# Blow_out_LED_tree_-_test_circuit_v1.net
KiCad netlist of a schematic drawn in EAGLE
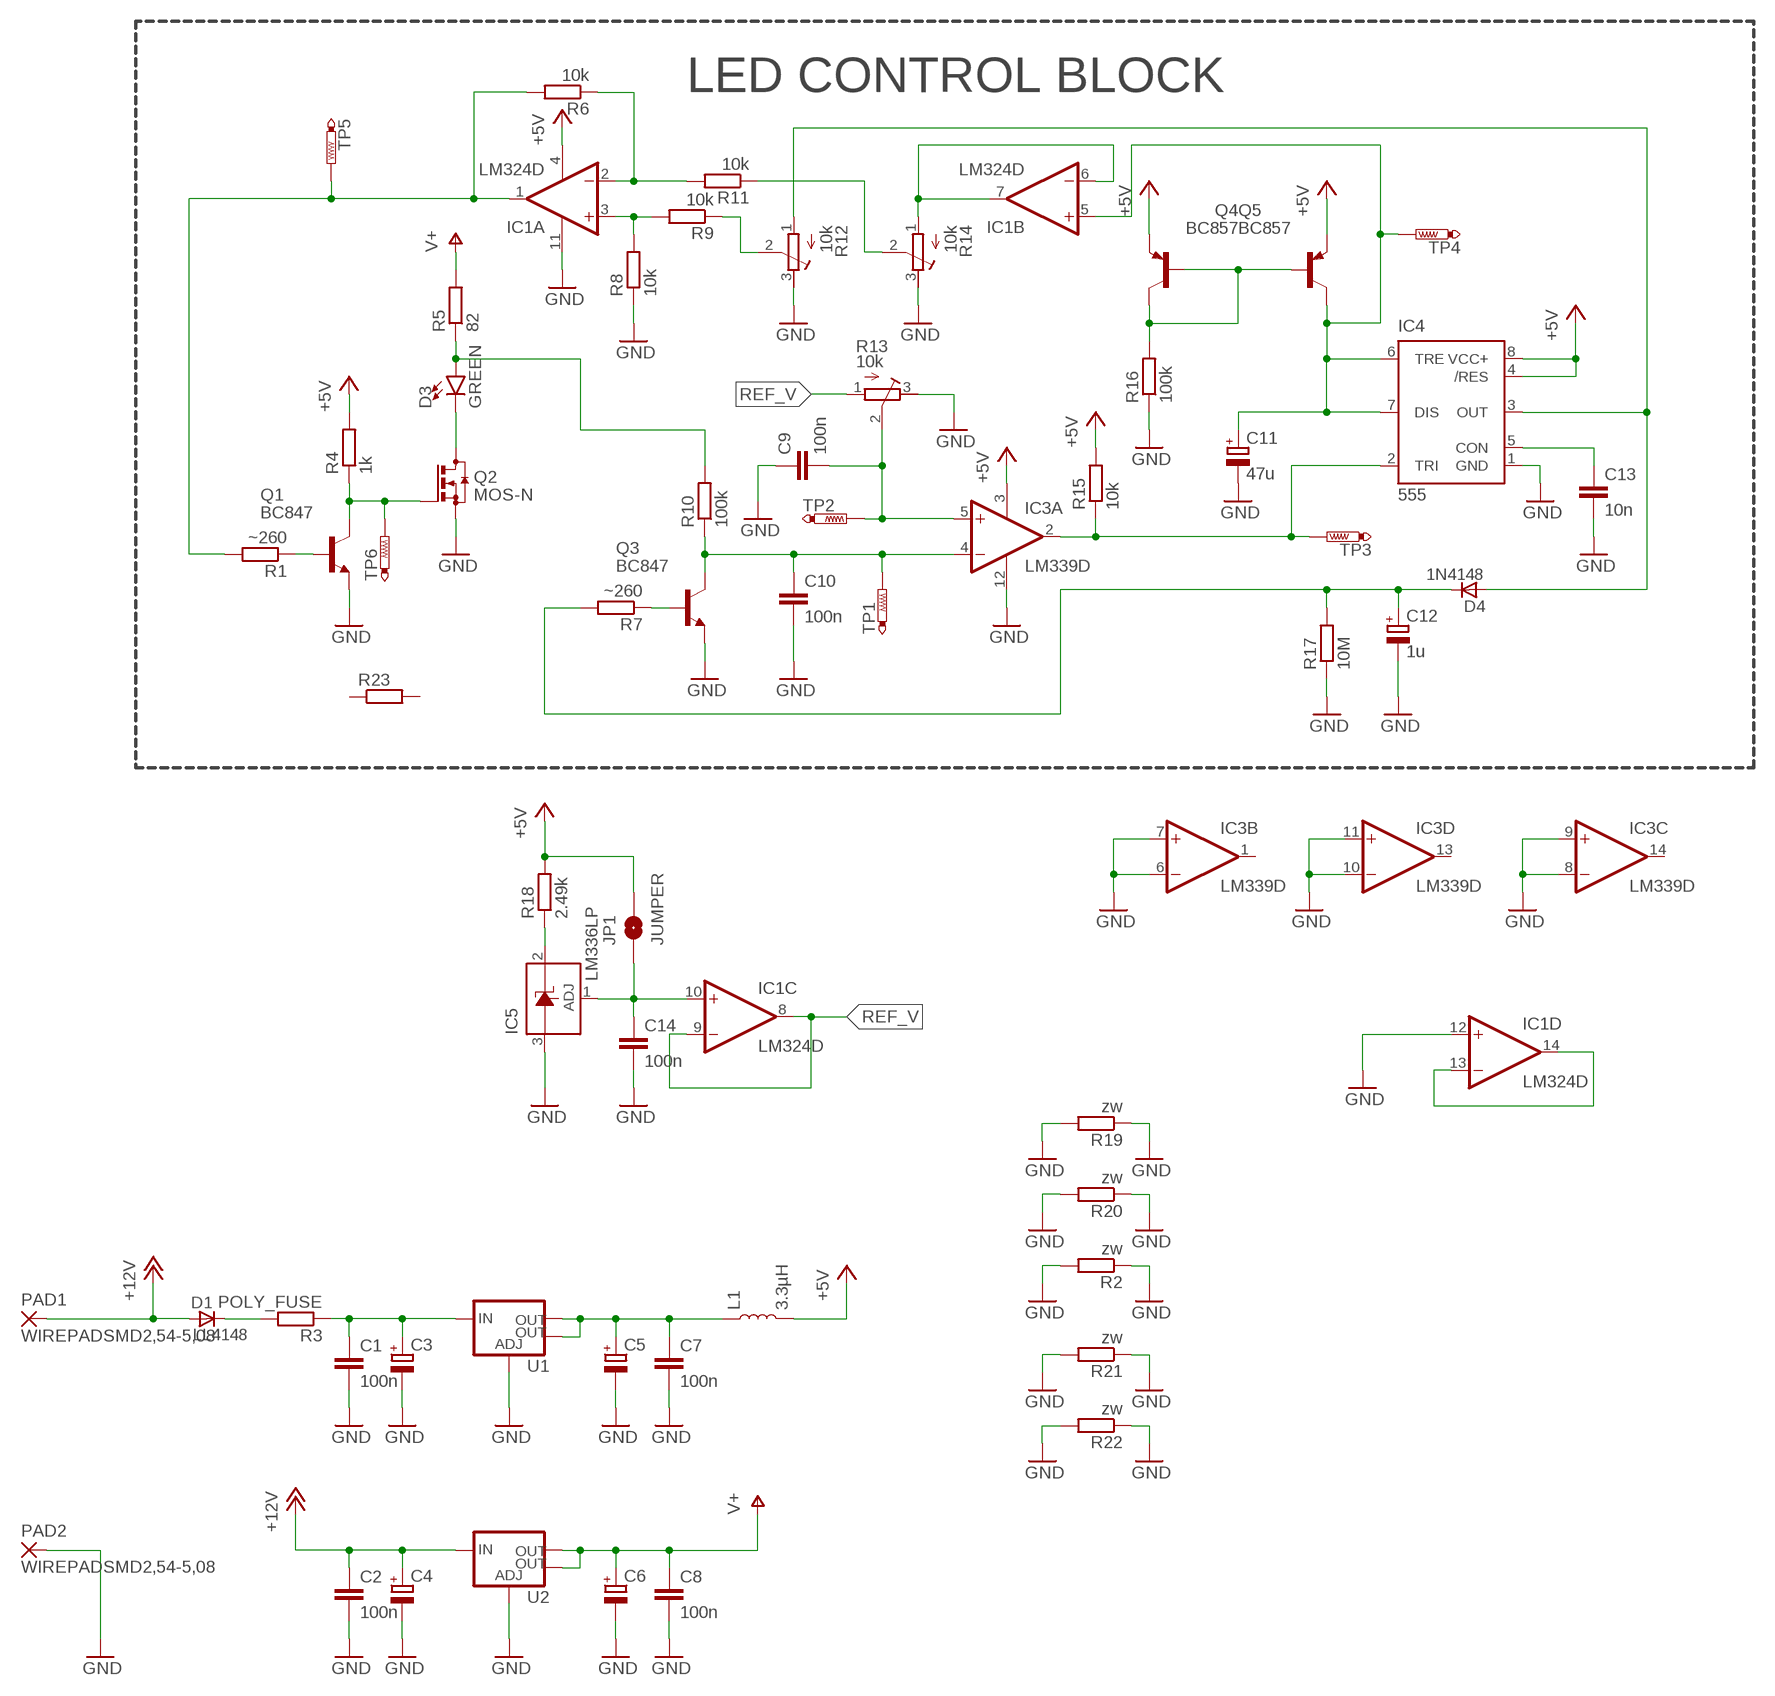
[diagram p0: schematic, sheet 1]

(export (version "E")
  (design (tool "Eeschema 10.0.6"))
  (components
    (comp (ref "C1")
      (value "100n")
      (footprint "eagle-import:C1206")
      (libsource (lib "eagle-import") (part "C-EUC1206"))
    )
    (comp (ref "C2")
      (value "100n")
      (footprint "eagle-import:C1206")
      (libsource (lib "eagle-import") (part "C-EUC1206"))
    )
    (comp (ref "C3")
      (value "CPOL-EU153CLV-0810")
      (footprint "eagle-import:153CLV-0810")
      (libsource (lib "eagle-import") (part "CPOL-EU153CLV-0810"))
    )
    (comp (ref "C4")
      (value "CPOL-EU153CLV-0810")
      (footprint "eagle-import:153CLV-0810")
      (libsource (lib "eagle-import") (part "CPOL-EU153CLV-0810"))
    )
    (comp (ref "C5")
      (value "CPOL-EU153CLV-0810")
      (footprint "eagle-import:153CLV-0810")
      (libsource (lib "eagle-import") (part "CPOL-EU153CLV-0810"))
    )
    (comp (ref "C6")
      (value "CPOL-EU153CLV-0810")
      (footprint "eagle-import:153CLV-0810")
      (libsource (lib "eagle-import") (part "CPOL-EU153CLV-0810"))
    )
    (comp (ref "C7")
      (value "100n")
      (footprint "eagle-import:C1206")
      (libsource (lib "eagle-import") (part "C-EUC1206"))
    )
    (comp (ref "C8")
      (value "100n")
      (footprint "eagle-import:C1206")
      (libsource (lib "eagle-import") (part "C-EUC1206"))
    )
    (comp (ref "C9")
      (value "100n")
      (footprint "eagle-import:C1206")
      (libsource (lib "eagle-import") (part "C-EUC1206"))
    )
    (comp (ref "C10")
      (value "100n")
      (footprint "eagle-import:C1206")
      (libsource (lib "eagle-import") (part "C-EUC1206"))
    )
    (comp (ref "C11")
      (value "47u")
      (footprint "eagle-import:153CLV-0605")
      (libsource (lib "eagle-import") (part "CPOL-EU153CLV-0605"))
    )
    (comp (ref "C12")
      (value "1u")
      (footprint "eagle-import:153CLV-0605")
      (libsource (lib "eagle-import") (part "CPOL-EU153CLV-0605"))
    )
    (comp (ref "C13")
      (value "10n")
      (footprint "eagle-import:C1206")
      (libsource (lib "eagle-import") (part "C-EUC1206"))
    )
    (comp (ref "C14")
      (value "100n")
      (footprint "eagle-import:C1206")
      (libsource (lib "eagle-import") (part "C-EUC1206"))
    )
    (comp (ref "D1")
      (value "LL4148")
      (footprint "eagle-import:SOD80_DO213AA_MINIMELF")
      (libsource (lib "eagle-import") (part "LL4148"))
    )
    (comp (ref "D3")
      (value "GREEN")
      (footprint "eagle-import:FKIT-LED-1206")
      (libsource (lib "eagle-import") (part "LED-FKIT-1206"))
    )
    (comp (ref "D4")
      (value "1N4148")
      (footprint "eagle-import:SOD80_DO213AA_MINIMELF")
      (libsource (lib "eagle-import") (part "LL4148"))
    )
    (comp (ref "IC1")
      (value "LM324D")
      (footprint "eagle-import:SO14")
      (libsource (lib "eagle-import") (part "LM324D"))
    )
    (comp (ref "IC3")
      (value "LM339D")
      (footprint "eagle-import:SO14")
      (libsource (lib "eagle-import") (part "LM339D"))
    )
    (comp (ref "IC4")
      (value "555")
      (footprint "eagle-import:SO08")
      (libsource (lib "eagle-import") (part "555D"))
    )
    (comp (ref "IC5")
      (value "LM336LP")
      (footprint "eagle-import:TO92")
      (libsource (lib "eagle-import") (part "LM336LP"))
    )
    (comp (ref "JP1")
      (value "JUMPER")
      (footprint "eagle-import:SMT-JUMPER_2_NO_NO-SILK_ROUND")
      (libsource (lib "eagle-import") (part "JUMPER-SMT_2_NO_NO-SILK_ROUND"))
    )
    (comp (ref "L1")
      (value "3.3µH")
      (footprint "eagle-import:0805")
      (libsource (lib "eagle-import") (part "INDUCTOR-0805-3.3UH"))
    )
    (comp (ref "PAD1")
      (value "WIREPADSMD2,54-5,08")
      (footprint "eagle-import:SMD2,54-5,08")
      (libsource (lib "eagle-import") (part "WIREPADSMD2,54-5,08"))
    )
    (comp (ref "PAD2")
      (value "WIREPADSMD2,54-5,08")
      (footprint "eagle-import:SMD2,54-5,08")
      (libsource (lib "eagle-import") (part "WIREPADSMD2,54-5,08"))
    )
    (comp (ref "Q1")
      (value "BC847")
      (footprint "eagle-import:SOT23")
      (libsource (lib "eagle-import") (part "BC847SMDA"))
    )
    (comp (ref "Q2")
      (value "MOS-N")
      (footprint "eagle-import:SOT23")
      (libsource (lib "eagle-import") (part "BSS123"))
    )
    (comp (ref "Q3")
      (value "BC847")
      (footprint "eagle-import:SOT23")
      (libsource (lib "eagle-import") (part "BC847SMDA"))
    )
    (comp (ref "Q4")
      (value "BC857")
      (footprint "eagle-import:SOT23-BEC")
      (libsource (lib "eagle-import") (part "BC857SMDALT1"))
    )
    (comp (ref "Q5")
      (value "BC857")
      (footprint "eagle-import:SOT23-BEC")
      (libsource (lib "eagle-import") (part "BC857SMDALT1"))
    )
    (comp (ref "R1")
      (value "~260")
      (footprint "eagle-import:R1206")
      (libsource (lib "eagle-import") (part "R-EU_R1206"))
    )
    (comp (ref "R2")
      (value "zw")
      (footprint "eagle-import:R1206")
      (libsource (lib "eagle-import") (part "R-EU_R1206"))
    )
    (comp (ref "R3")
      (value "POLY_FUSE")
      (footprint "eagle-import:R1206")
      (libsource (lib "eagle-import") (part "R-EU_R1206"))
    )
    (comp (ref "R4")
      (value "1k")
      (footprint "eagle-import:R1206")
      (libsource (lib "eagle-import") (part "R-EU_R1206"))
    )
    (comp (ref "R5")
      (value "82")
      (footprint "eagle-import:R1206")
      (libsource (lib "eagle-import") (part "R-EU_R1206"))
    )
    (comp (ref "R6")
      (value "10k")
      (footprint "eagle-import:R1206")
      (libsource (lib "eagle-import") (part "R-EU_R1206"))
    )
    (comp (ref "R7")
      (value "~260")
      (footprint "eagle-import:R1206")
      (libsource (lib "eagle-import") (part "R-EU_R1206"))
    )
    (comp (ref "R8")
      (value "10k")
      (footprint "eagle-import:R1206")
      (libsource (lib "eagle-import") (part "R-EU_R1206"))
    )
    (comp (ref "R9")
      (value "10k")
      (footprint "eagle-import:R1206")
      (libsource (lib "eagle-import") (part "R-EU_R1206"))
    )
    (comp (ref "R10")
      (value "100k")
      (footprint "eagle-import:R1206")
      (libsource (lib "eagle-import") (part "R-EU_R1206"))
    )
    (comp (ref "R11")
      (value "10k")
      (footprint "eagle-import:R1206")
      (libsource (lib "eagle-import") (part "R-EU_R1206"))
    )
    (comp (ref "R12")
      (value "10k")
      (footprint "eagle-import:RTRIM3374")
      (libsource (lib "eagle-import") (part "R-TRIMM3374"))
    )
    (comp (ref "R13")
      (value "10k")
      (footprint "eagle-import:RTRIM3374")
      (libsource (lib "eagle-import") (part "R-TRIMM3374"))
    )
    (comp (ref "R14")
      (value "10k")
      (footprint "eagle-import:RTRIM3374")
      (libsource (lib "eagle-import") (part "R-TRIMM3374"))
    )
    (comp (ref "R15")
      (value "10k")
      (footprint "eagle-import:R1206")
      (libsource (lib "eagle-import") (part "R-EU_R1206"))
    )
    (comp (ref "R16")
      (value "100k")
      (footprint "eagle-import:R1206")
      (libsource (lib "eagle-import") (part "R-EU_R1206"))
    )
    (comp (ref "R17")
      (value "10M")
      (footprint "eagle-import:R1206")
      (libsource (lib "eagle-import") (part "R-EU_R1206"))
    )
    (comp (ref "R18")
      (value "2.49k")
      (footprint "eagle-import:R1206")
      (libsource (lib "eagle-import") (part "R-EU_R1206"))
    )
    (comp (ref "R19")
      (value "zw")
      (footprint "eagle-import:R1206")
      (libsource (lib "eagle-import") (part "R-EU_R1206"))
    )
    (comp (ref "R20")
      (value "zw")
      (footprint "eagle-import:R1206")
      (libsource (lib "eagle-import") (part "R-EU_R1206"))
    )
    (comp (ref "R21")
      (value "zw")
      (footprint "eagle-import:R1206")
      (libsource (lib "eagle-import") (part "R-EU_R1206"))
    )
    (comp (ref "R22")
      (value "zw")
      (footprint "eagle-import:R1206")
      (libsource (lib "eagle-import") (part "R-EU_R1206"))
    )
    (comp (ref "R23")
      (value "R-EU_R0603")
      (footprint "eagle-import:R0603")
      (libsource (lib "eagle-import") (part "R-EU_R0603"))
    )
    (comp (ref "TP1")
      (value "PTR1B2,54")
      (footprint "eagle-import:B2,54")
      (libsource (lib "eagle-import") (part "PTR1B2,54"))
    )
    (comp (ref "TP2")
      (value "PTR1B2,54")
      (footprint "eagle-import:B2,54")
      (libsource (lib "eagle-import") (part "PTR1B2,54"))
    )
    (comp (ref "TP3")
      (value "PTR1B2,54")
      (footprint "eagle-import:B2,54")
      (libsource (lib "eagle-import") (part "PTR1B2,54"))
    )
    (comp (ref "TP4")
      (value "PTR1B2,54")
      (footprint "eagle-import:B2,54")
      (libsource (lib "eagle-import") (part "PTR1B2,54"))
    )
    (comp (ref "TP5")
      (value "PTR1B2,54")
      (footprint "eagle-import:B2,54")
      (libsource (lib "eagle-import") (part "PTR1B2,54"))
    )
    (comp (ref "TP6")
      (value "PTR1B2,54")
      (footprint "eagle-import:B2,54")
      (libsource (lib "eagle-import") (part "PTR1B2,54"))
    )
    (comp (ref "U1")
      (value "V_REG_LM1117SOT223")
      (footprint "eagle-import:SOT223")
      (libsource (lib "eagle-import") (part "V_REG_LM1117SOT223"))
    )
    (comp (ref "U2")
      (value "V_REG_LM1117SOT223")
      (footprint "eagle-import:SOT223")
      (libsource (lib "eagle-import") (part "V_REG_LM1117SOT223"))
    )
  )
  (nets
    (net (code "1") (name "+5V") (class "Default")
      (node (ref "IC1") (pin "4") (pinfunction "V+_4") (pintype "power_in"))
      (node (ref "IC3") (pin "3") (pinfunction "V+_3") (pintype "power_in"))
      (node (ref "IC4") (pin "4") (pinfunction "/RES_4") (pintype "input"))
      (node (ref "IC4") (pin "8") (pinfunction "VCC+_8") (pintype "power_in"))
      (node (ref "JP1") (pin "2") (pinfunction "2_2") (pintype "passive"))
      (node (ref "L1") (pin "2") (pinfunction "2_2") (pintype "passive"))
      (node (ref "Q4") (pin "E") (pinfunction "E_E") (pintype "passive"))
      (node (ref "Q5") (pin "E") (pinfunction "E_E") (pintype "passive"))
      (node (ref "R15") (pin "2") (pinfunction "2_2") (pintype "passive"))
      (node (ref "R18") (pin "2") (pinfunction "2_2") (pintype "passive"))
      (node (ref "R4") (pin "2") (pinfunction "2_2") (pintype "passive"))
    )
    (net (code "2") (name "+12V") (class "Default")
      (node (ref "C2") (pin "1") (pinfunction "1_1") (pintype "passive"))
      (node (ref "C4") (pin "+") (pinfunction "+_+") (pintype "passive"))
      (node (ref "D1") (pin "A") (pinfunction "A_A") (pintype "passive"))
      (node (ref "PAD1") (pin "1") (pinfunction "P_1") (pintype "passive"))
      (node (ref "U2") (pin "3") (pinfunction "IN_3") (pintype "input"))
    )
    (net (code "3") (name "GND") (class "Default")
      (node (ref "C1") (pin "2") (pinfunction "2_2") (pintype "passive"))
      (node (ref "C10") (pin "2") (pinfunction "2_2") (pintype "passive"))
      (node (ref "C11") (pin "-") (pinfunction "-_-") (pintype "passive"))
      (node (ref "C12") (pin "-") (pinfunction "-_-") (pintype "passive"))
      (node (ref "C13") (pin "2") (pinfunction "2_2") (pintype "passive"))
      (node (ref "C14") (pin "2") (pinfunction "2_2") (pintype "passive"))
      (node (ref "C2") (pin "2") (pinfunction "2_2") (pintype "passive"))
      (node (ref "C3") (pin "-") (pinfunction "-_-") (pintype "passive"))
      (node (ref "C4") (pin "-") (pinfunction "-_-") (pintype "passive"))
      (node (ref "C5") (pin "-") (pinfunction "-_-") (pintype "passive"))
      (node (ref "C6") (pin "-") (pinfunction "-_-") (pintype "passive"))
      (node (ref "C7") (pin "2") (pinfunction "2_2") (pintype "passive"))
      (node (ref "C8") (pin "2") (pinfunction "2_2") (pintype "passive"))
      (node (ref "C9") (pin "1") (pinfunction "1_1") (pintype "passive"))
      (node (ref "IC1") (pin "11") (pinfunction "V-_11") (pintype "power_in"))
      (node (ref "IC1") (pin "12") (pinfunction "+IN_12") (pintype "input"))
      (node (ref "IC3") (pin "10") (pinfunction "-IN_10") (pintype "input"))
      (node (ref "IC3") (pin "11") (pinfunction "+IN_11") (pintype "input"))
      (node (ref "IC3") (pin "12") (pinfunction "GND_12") (pintype "power_in"))
      (node (ref "IC3") (pin "6") (pinfunction "-IN_6") (pintype "input"))
      (node (ref "IC3") (pin "7") (pinfunction "+IN_7") (pintype "input"))
      (node (ref "IC3") (pin "8") (pinfunction "-IN_8") (pintype "input"))
      (node (ref "IC3") (pin "9") (pinfunction "+IN_9") (pintype "input"))
      (node (ref "IC4") (pin "1") (pinfunction "GND_1") (pintype "power_in"))
      (node (ref "IC5") (pin "3") (pinfunction "A_3") (pintype "input"))
      (node (ref "PAD2") (pin "1") (pinfunction "P_1") (pintype "passive"))
      (node (ref "Q1") (pin "2") (pinfunction "E_2") (pintype "passive"))
      (node (ref "Q2") (pin "2") (pinfunction "S_2") (pintype "passive"))
      (node (ref "Q3") (pin "2") (pinfunction "E_2") (pintype "passive"))
      (node (ref "R12") (pin "3") (pinfunction "E_3") (pintype "passive"))
      (node (ref "R13") (pin "3") (pinfunction "E_3") (pintype "passive"))
      (node (ref "R14") (pin "3") (pinfunction "E_3") (pintype "passive"))
      (node (ref "R16") (pin "1") (pinfunction "1_1") (pintype "passive"))
      (node (ref "R17") (pin "1") (pinfunction "1_1") (pintype "passive"))
      (node (ref "R19") (pin "1") (pinfunction "1_1") (pintype "passive"))
      (node (ref "R19") (pin "2") (pinfunction "2_2") (pintype "passive"))
      (node (ref "R2") (pin "1") (pinfunction "1_1") (pintype "passive"))
      (node (ref "R2") (pin "2") (pinfunction "2_2") (pintype "passive"))
      (node (ref "R20") (pin "1") (pinfunction "1_1") (pintype "passive"))
      (node (ref "R20") (pin "2") (pinfunction "2_2") (pintype "passive"))
      (node (ref "R21") (pin "1") (pinfunction "1_1") (pintype "passive"))
      (node (ref "R21") (pin "2") (pinfunction "2_2") (pintype "passive"))
      (node (ref "R22") (pin "1") (pinfunction "1_1") (pintype "passive"))
      (node (ref "R22") (pin "2") (pinfunction "2_2") (pintype "passive"))
      (node (ref "R8") (pin "1") (pinfunction "1_1") (pintype "passive"))
      (node (ref "U1") (pin "1") (pinfunction "ADJ_1") (pintype "input"))
      (node (ref "U2") (pin "1") (pinfunction "ADJ_1") (pintype "input"))
    )
    (net (code "4") (name "Net-(C5-Pad+)") (class "Default")
      (node (ref "C5") (pin "+") (pinfunction "+_+") (pintype "passive"))
      (node (ref "C7") (pin "1") (pinfunction "1_1") (pintype "passive"))
      (node (ref "L1") (pin "1") (pinfunction "1_1") (pintype "passive"))
      (node (ref "U1") (pin "2") (pinfunction "OUT_2") (pintype "output"))
      (node (ref "U1") (pin "4") (pinfunction "OUT_4") (pintype "output"))
    )
    (net (code "5") (name "Net-(C12-Pad+)") (class "Default")
      (node (ref "C12") (pin "+") (pinfunction "+_+") (pintype "passive"))
      (node (ref "D4") (pin "C") (pinfunction "C_C") (pintype "passive"))
      (node (ref "R17") (pin "2") (pinfunction "2_2") (pintype "passive"))
      (node (ref "R7") (pin "2") (pinfunction "2_2") (pintype "passive"))
    )
    (net (code "6") (name "Net-(D1-PadC)") (class "Default")
      (node (ref "D1") (pin "C") (pinfunction "C_C") (pintype "passive"))
      (node (ref "R3") (pin "2") (pinfunction "2_2") (pintype "passive"))
    )
    (net (code "7") (name "Net-(D3-PadA)") (class "Default")
      (node (ref "D3") (pin "A") (pinfunction "A_A") (pintype "passive"))
      (node (ref "R10") (pin "2") (pinfunction "2_2") (pintype "passive"))
      (node (ref "R5") (pin "1") (pinfunction "1_1") (pintype "passive"))
    )
    (net (code "8") (name "Net-(IC1A-+IN)") (class "Default")
      (node (ref "IC1") (pin "3") (pinfunction "+IN_3") (pintype "input"))
      (node (ref "R8") (pin "2") (pinfunction "2_2") (pintype "passive"))
      (node (ref "R9") (pin "2") (pinfunction "2_2") (pintype "passive"))
    )
    (net (code "9") (name "Net-(IC1A--IN)") (class "Default")
      (node (ref "IC1") (pin "2") (pinfunction "-IN_2") (pintype "input"))
      (node (ref "R11") (pin "2") (pinfunction "2_2") (pintype "passive"))
      (node (ref "R6") (pin "1") (pinfunction "1_1") (pintype "passive"))
    )
    (net (code "10") (name "Net-(IC1A-OUT)") (class "Default")
      (node (ref "IC1") (pin "1") (pinfunction "OUT_1") (pintype "output"))
      (node (ref "R1") (pin "2") (pinfunction "2_2") (pintype "passive"))
      (node (ref "R6") (pin "2") (pinfunction "2_2") (pintype "passive"))
      (node (ref "TP5") (pin "TP") (pinfunction "TP_TP") (pintype "input"))
    )
    (net (code "11") (name "Net-(IC1B-+IN)") (class "Default")
      (node (ref "C11") (pin "+") (pinfunction "+_+") (pintype "passive"))
      (node (ref "IC1") (pin "5") (pinfunction "+IN_5") (pintype "input"))
      (node (ref "IC4") (pin "6") (pinfunction "TRE_6") (pintype "input"))
      (node (ref "IC4") (pin "7") (pinfunction "DIS_7") (pintype "input"))
      (node (ref "Q5") (pin "C") (pinfunction "C_C") (pintype "passive"))
      (node (ref "TP4") (pin "TP") (pinfunction "TP_TP") (pintype "input"))
    )
    (net (code "12") (name "Net-(IC1B--IN)") (class "Default")
      (node (ref "IC1") (pin "6") (pinfunction "-IN_6") (pintype "input"))
      (node (ref "IC1") (pin "7") (pinfunction "OUT_7") (pintype "output"))
      (node (ref "R14") (pin "1") (pinfunction "A_1") (pintype "passive"))
    )
    (net (code "13") (name "Net-(IC1C-+IN)") (class "Default")
      (node (ref "C14") (pin "1") (pinfunction "1_1") (pintype "passive"))
      (node (ref "IC1") (pin "10") (pinfunction "+IN_10") (pintype "input"))
      (node (ref "IC5") (pin "1") (pinfunction "ADJ_1") (pintype "input"))
      (node (ref "JP1") (pin "1") (pinfunction "1_1") (pintype "passive"))
    )
    (net (code "14") (name "Net-(IC1D--IN)") (class "Default")
      (node (ref "IC1") (pin "13") (pinfunction "-IN_13") (pintype "input"))
      (node (ref "IC1") (pin "14") (pinfunction "OUT_14") (pintype "output"))
    )
    (net (code "15") (name "Net-(IC3A-+IN)") (class "Default")
      (node (ref "C9") (pin "2") (pinfunction "2_2") (pintype "passive"))
      (node (ref "IC3") (pin "5") (pinfunction "+IN_5") (pintype "input"))
      (node (ref "R13") (pin "2") (pinfunction "S_2") (pintype "passive"))
      (node (ref "TP2") (pin "TP") (pinfunction "TP_TP") (pintype "input"))
    )
    (net (code "16") (name "Net-(IC3A--IN)") (class "Default")
      (node (ref "C10") (pin "1") (pinfunction "1_1") (pintype "passive"))
      (node (ref "IC3") (pin "4") (pinfunction "-IN_4") (pintype "input"))
      (node (ref "Q3") (pin "3") (pinfunction "C_3") (pintype "passive"))
      (node (ref "R10") (pin "1") (pinfunction "1_1") (pintype "passive"))
      (node (ref "TP1") (pin "TP") (pinfunction "TP_TP") (pintype "input"))
    )
    (net (code "17") (name "Net-(IC3A-OUT)") (class "Default")
      (node (ref "IC3") (pin "2") (pinfunction "OUT_2") (pintype "open_collector"))
      (node (ref "IC4") (pin "2") (pinfunction "TRI_2") (pintype "input"))
      (node (ref "R15") (pin "1") (pinfunction "1_1") (pintype "passive"))
      (node (ref "TP3") (pin "TP") (pinfunction "TP_TP") (pintype "input"))
    )
    (net (code "18") (name "Net-(IC4-CON)") (class "Default")
      (node (ref "C13") (pin "1") (pinfunction "1_1") (pintype "passive"))
      (node (ref "IC4") (pin "5") (pinfunction "CON_5") (pintype "input"))
    )
    (net (code "19") (name "Net-(IC4-OUT)") (class "Default")
      (node (ref "D4") (pin "A") (pinfunction "A_A") (pintype "passive"))
      (node (ref "IC4") (pin "3") (pinfunction "OUT_3") (pintype "output"))
      (node (ref "R12") (pin "1") (pinfunction "A_1") (pintype "passive"))
    )
    (net (code "20") (name "Net-(IC5-C)") (class "Default")
      (node (ref "IC5") (pin "2") (pinfunction "C_2") (pintype "passive"))
      (node (ref "R18") (pin "1") (pinfunction "1_1") (pintype "passive"))
    )
    (net (code "21") (name "Net-(Q1-B)") (class "Default")
      (node (ref "Q1") (pin "1") (pinfunction "B_1") (pintype "passive"))
      (node (ref "R1") (pin "1") (pinfunction "1_1") (pintype "passive"))
    )
    (net (code "22") (name "Net-(Q1-C)") (class "Default")
      (node (ref "Q1") (pin "3") (pinfunction "C_3") (pintype "passive"))
      (node (ref "Q2") (pin "1") (pinfunction "G_1") (pintype "passive"))
      (node (ref "R4") (pin "1") (pinfunction "1_1") (pintype "passive"))
      (node (ref "TP6") (pin "TP") (pinfunction "TP_TP") (pintype "input"))
    )
    (net (code "23") (name "Net-(Q2-D)") (class "Default")
      (node (ref "D3") (pin "C") (pinfunction "C_C") (pintype "passive"))
      (node (ref "Q2") (pin "3") (pinfunction "D_3") (pintype "passive"))
    )
    (net (code "24") (name "Net-(Q3-B)") (class "Default")
      (node (ref "Q3") (pin "1") (pinfunction "B_1") (pintype "passive"))
      (node (ref "R7") (pin "1") (pinfunction "1_1") (pintype "passive"))
    )
    (net (code "25") (name "Net-(Q4-PadB)") (class "Default")
      (node (ref "Q4") (pin "B") (pinfunction "B_B") (pintype "passive"))
      (node (ref "Q4") (pin "C") (pinfunction "C_C") (pintype "passive"))
      (node (ref "Q5") (pin "B") (pinfunction "B_B") (pintype "passive"))
      (node (ref "R16") (pin "2") (pinfunction "2_2") (pintype "passive"))
    )
    (net (code "26") (name "Net-(R12-S)") (class "Default")
      (node (ref "R12") (pin "2") (pinfunction "S_2") (pintype "passive"))
      (node (ref "R9") (pin "1") (pinfunction "1_1") (pintype "passive"))
    )
    (net (code "27") (name "Net-(R14-S)") (class "Default")
      (node (ref "R11") (pin "1") (pinfunction "1_1") (pintype "passive"))
      (node (ref "R14") (pin "2") (pinfunction "S_2") (pintype "passive"))
    )
    (net (code "28") (name "Net-(U1-IN)") (class "Default")
      (node (ref "C1") (pin "1") (pinfunction "1_1") (pintype "passive"))
      (node (ref "C3") (pin "+") (pinfunction "+_+") (pintype "passive"))
      (node (ref "R3") (pin "1") (pinfunction "1_1") (pintype "passive"))
      (node (ref "U1") (pin "3") (pinfunction "IN_3") (pintype "input"))
    )
    (net (code "29") (name "REF_V") (class "Default")
      (node (ref "IC1") (pin "8") (pinfunction "OUT_8") (pintype "output"))
      (node (ref "IC1") (pin "9") (pinfunction "-IN_9") (pintype "input"))
      (node (ref "R13") (pin "1") (pinfunction "A_1") (pintype "passive"))
    )
    (net (code "30") (name "V+") (class "Default")
      (node (ref "C6") (pin "+") (pinfunction "+_+") (pintype "passive"))
      (node (ref "C8") (pin "1") (pinfunction "1_1") (pintype "passive"))
      (node (ref "R5") (pin "2") (pinfunction "2_2") (pintype "passive"))
      (node (ref "U2") (pin "2") (pinfunction "OUT_2") (pintype "output"))
      (node (ref "U2") (pin "4") (pinfunction "OUT_4") (pintype "output"))
    )
    (net (code "31") (name "unconnected-(IC3B-OUT-Pad1)") (class "Default")
      (node (ref "IC3") (pin "1") (pinfunction "OUT_1") (pintype "open_collector"))
    )
    (net (code "32") (name "unconnected-(IC3C-OUT-Pad14)") (class "Default")
      (node (ref "IC3") (pin "14") (pinfunction "OUT_14") (pintype "open_collector"))
    )
    (net (code "33") (name "unconnected-(IC3D-OUT-Pad13)") (class "Default")
      (node (ref "IC3") (pin "13") (pinfunction "OUT_13") (pintype "open_collector"))
    )
    (net (code "34") (name "unconnected-(R23-Pad1)") (class "Default")
      (node (ref "R23") (pin "1") (pinfunction "1_1") (pintype "passive"))
    )
    (net (code "35") (name "unconnected-(R23-Pad2)") (class "Default")
      (node (ref "R23") (pin "2") (pinfunction "2_2") (pintype "passive"))
    )
  )
)
